# TPS53819A-5v.net
KiCad netlist of a schematic drawn in EAGLE
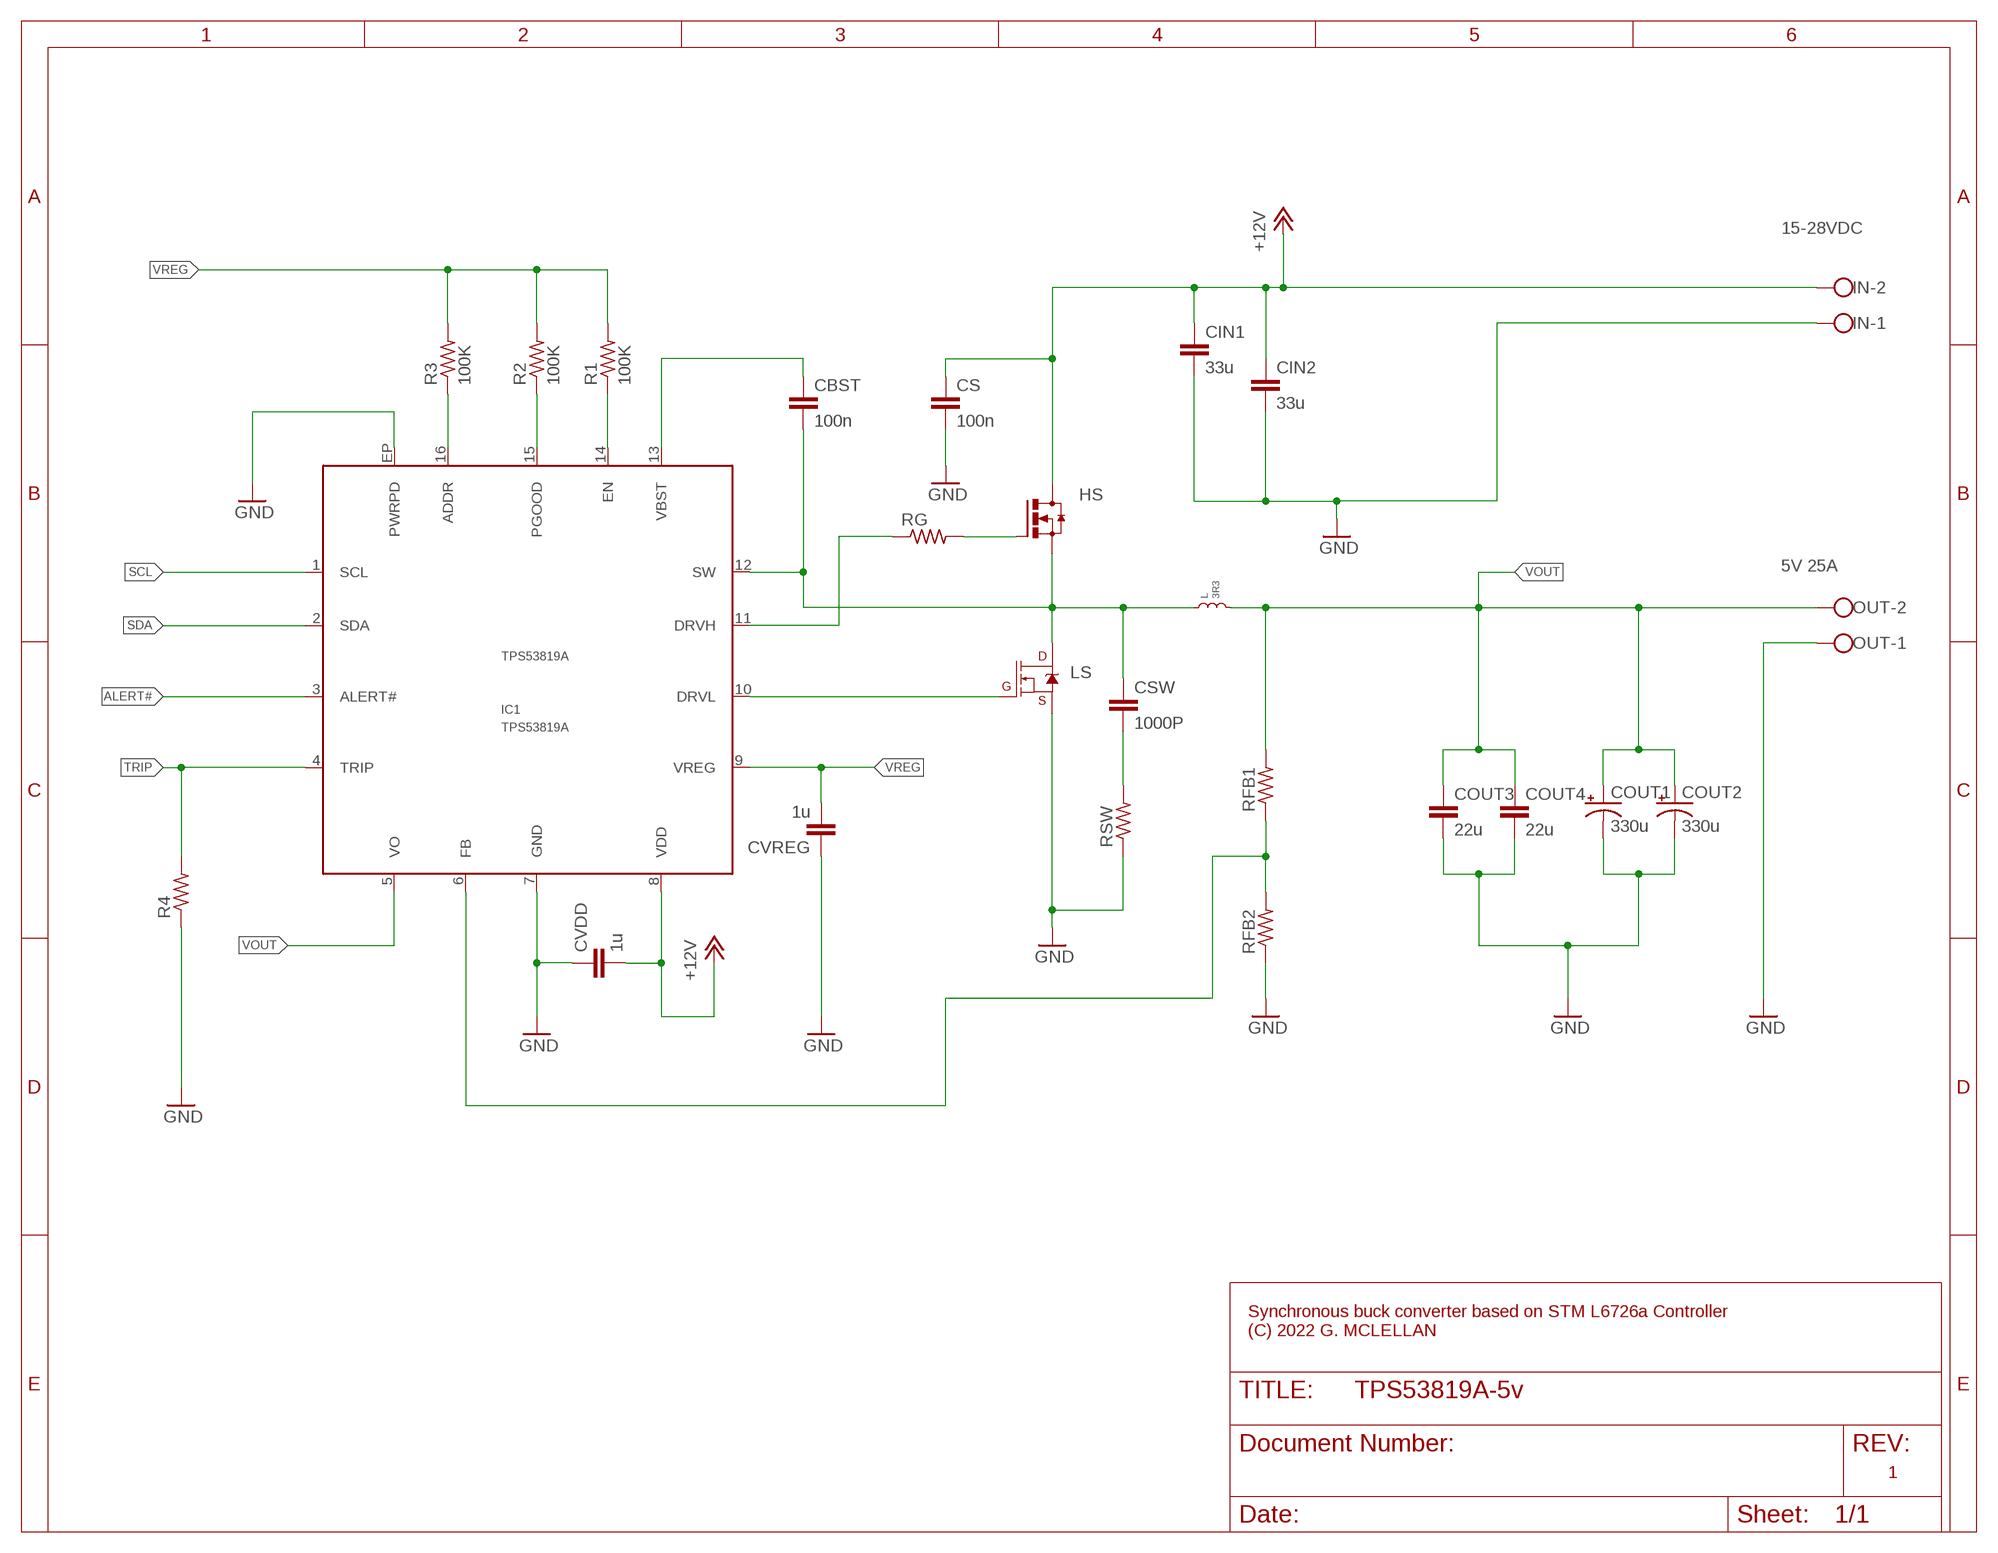
[diagram p0: schematic, sheet 1]

(export (version "E")
  (design (tool "Eeschema 10.0.6"))
  (components
    (comp (ref "CBST")
      (value "100n")
      (footprint "eagle-import:C0603")
      (libsource (lib "eagle-import") (part "C-EUC0603"))
    )
    (comp (ref "CIN1")
      (value "33u")
      (footprint "eagle-import:C2220K")
      (libsource (lib "eagle-import") (part "C-EUC2220K"))
    )
    (comp (ref "CIN2")
      (value "33u")
      (footprint "eagle-import:C2220K")
      (libsource (lib "eagle-import") (part "C-EUC2220K"))
    )
    (comp (ref "COUT1")
      (value "330u")
      (footprint "eagle-import:SANYO-OSCON_SMD_C6")
      (libsource (lib "eagle-import") (part "CPOL-USSANYO_SMD_C6"))
    )
    (comp (ref "COUT2")
      (value "330u")
      (footprint "eagle-import:SANYO-OSCON_SMD_C6")
      (libsource (lib "eagle-import") (part "CPOL-USSANYO_SMD_C6"))
    )
    (comp (ref "COUT3")
      (value "22u")
      (footprint "eagle-import:C1206")
      (libsource (lib "eagle-import") (part "C-EUC1206"))
    )
    (comp (ref "COUT4")
      (value "22u")
      (footprint "eagle-import:C1206")
      (libsource (lib "eagle-import") (part "C-EUC1206"))
    )
    (comp (ref "CS")
      (value "100n")
      (footprint "eagle-import:C0805")
      (libsource (lib "eagle-import") (part "C-EUC0805"))
    )
    (comp (ref "CSW")
      (value "1000P")
      (footprint "eagle-import:C0603")
      (libsource (lib "eagle-import") (part "C-EUC0603"))
    )
    (comp (ref "CVDD")
      (value "1u")
      (footprint "eagle-import:C0805")
      (libsource (lib "eagle-import") (part "C-EUC0805"))
    )
    (comp (ref "CVREG")
      (value "1u")
      (footprint "eagle-import:C0603")
      (libsource (lib "eagle-import") (part "C-EUC0603"))
    )
    (comp (ref "HS")
      (value "N_MOSFET_POWERSO8")
      (footprint "eagle-import:POWERSO8")
      (libsource (lib "eagle-import") (part "N_MOSFET_POWERSO8"))
    )
    (comp (ref "IC1")
      (value "TPS53819A")
      (footprint "eagle-import:QFN-16")
      (libsource (lib "eagle-import") (part "TPS53819A"))
    )
    (comp (ref "IN")
      (value "W237-102")
      (footprint "eagle-import:W237-102")
      (fields (field (name "MPN") "237-102"))
      (libsource (lib "eagle-import") (part "W237-102"))
    )
    (comp (ref "L")
      (value "3R3")
      (footprint "eagle-import:XAL1010")
      (libsource (lib "eagle-import") (part "INDUCTOR.XAL1010"))
    )
    (comp (ref "LS")
      (value "MOSFET-NCH-FDS6630A")
      (footprint "eagle-import:SO08")
      (libsource (lib "eagle-import") (part "MOSFET-NCH-FDS6630A"))
    )
    (comp (ref "OUT")
      (value "W237-102")
      (footprint "eagle-import:W237-102")
      (fields (field (name "MPN") "237-102"))
      (libsource (lib "eagle-import") (part "W237-102"))
    )
    (comp (ref "R1")
      (value "100K")
      (footprint "eagle-import:R0603")
      (libsource (lib "eagle-import") (part "R-US_R0603"))
    )
    (comp (ref "R2")
      (value "100K")
      (footprint "eagle-import:R0603")
      (libsource (lib "eagle-import") (part "R-US_R0603"))
    )
    (comp (ref "R3")
      (value "100K")
      (footprint "eagle-import:R0603")
      (libsource (lib "eagle-import") (part "R-US_R0603"))
    )
    (comp (ref "R4")
      (value "R-US_R0603")
      (footprint "eagle-import:R0603")
      (libsource (lib "eagle-import") (part "R-US_R0603"))
    )
    (comp (ref "RFB1")
      (value "R-US_R0805")
      (footprint "eagle-import:R0805")
      (libsource (lib "eagle-import") (part "R-US_R0805"))
    )
    (comp (ref "RFB2")
      (value "R-US_R0805")
      (footprint "eagle-import:R0805")
      (libsource (lib "eagle-import") (part "R-US_R0805"))
    )
    (comp (ref "RG")
      (value "R-US_R0603")
      (footprint "eagle-import:R0603")
      (libsource (lib "eagle-import") (part "R-US_R0603"))
    )
    (comp (ref "RSW")
      (value "R-US_R0603")
      (footprint "eagle-import:R0603")
      (libsource (lib "eagle-import") (part "R-US_R0603"))
    )
  )
  (nets
    (net (code "1") (name "+12V") (class "Default")
      (node (ref "CIN1") (pin "1") (pinfunction "1_1") (pintype "passive"))
      (node (ref "CIN2") (pin "1") (pinfunction "1_1") (pintype "passive"))
      (node (ref "CS") (pin "1") (pinfunction "1_1") (pintype "passive"))
      (node (ref "CVDD") (pin "2") (pinfunction "2_2") (pintype "passive"))
      (node (ref "HS") (pin "5") (pinfunction "D_5") (pintype "passive"))
      (node (ref "HS") (pin "6") (pinfunction "D_6") (pintype "passive"))
      (node (ref "HS") (pin "7") (pinfunction "D_7") (pintype "passive"))
      (node (ref "HS") (pin "8") (pinfunction "D_8") (pintype "passive"))
      (node (ref "HS") (pin "PAD") (pinfunction "D_PAD") (pintype "passive"))
      (node (ref "IC1") (pin "8") (pinfunction "VDD_8") (pintype "power_in"))
      (node (ref "IN") (pin "2") (pinfunction "KL_2") (pintype "passive"))
    )
    (net (code "2") (name "ALERT#") (class "Default")
      (node (ref "IC1") (pin "3") (pinfunction "ALERT#_3") (pintype "output"))
    )
    (net (code "3") (name "GND") (class "Default")
      (node (ref "CIN1") (pin "2") (pinfunction "2_2") (pintype "passive"))
      (node (ref "CIN2") (pin "2") (pinfunction "2_2") (pintype "passive"))
      (node (ref "COUT1") (pin "-") (pinfunction "-_-") (pintype "passive"))
      (node (ref "COUT2") (pin "-") (pinfunction "-_-") (pintype "passive"))
      (node (ref "COUT3") (pin "2") (pinfunction "2_2") (pintype "passive"))
      (node (ref "COUT4") (pin "2") (pinfunction "2_2") (pintype "passive"))
      (node (ref "CS") (pin "2") (pinfunction "2_2") (pintype "passive"))
      (node (ref "CVDD") (pin "1") (pinfunction "1_1") (pintype "passive"))
      (node (ref "CVREG") (pin "1") (pinfunction "1_1") (pintype "passive"))
      (node (ref "IC1") (pin "7") (pinfunction "GND_7") (pintype "power_in"))
      (node (ref "IC1") (pin "EP") (pinfunction "PWRPD_EP") (pintype "power_in"))
      (node (ref "IN") (pin "1") (pinfunction "KL_1") (pintype "passive"))
      (node (ref "LS") (pin "1") (pinfunction "S_1") (pintype "bidirectional"))
      (node (ref "LS") (pin "2") (pinfunction "S_2") (pintype "bidirectional"))
      (node (ref "LS") (pin "3") (pinfunction "S_3") (pintype "bidirectional"))
      (node (ref "OUT") (pin "1") (pinfunction "KL_1") (pintype "passive"))
      (node (ref "R4") (pin "1") (pinfunction "1_1") (pintype "passive"))
      (node (ref "RFB2") (pin "1") (pinfunction "1_1") (pintype "passive"))
      (node (ref "RSW") (pin "1") (pinfunction "1_1") (pintype "passive"))
    )
    (net (code "4") (name "Net-(CSW-Pad2)") (class "Default")
      (node (ref "CSW") (pin "2") (pinfunction "2_2") (pintype "passive"))
      (node (ref "RSW") (pin "2") (pinfunction "2_2") (pintype "passive"))
    )
    (net (code "5") (name "Net-(HS-G)") (class "Default")
      (node (ref "HS") (pin "4") (pinfunction "G_4") (pintype "passive"))
      (node (ref "RG") (pin "2") (pinfunction "2_2") (pintype "passive"))
    )
    (net (code "6") (name "Net-(IC1-ADDR)") (class "Default")
      (node (ref "IC1") (pin "16") (pinfunction "ADDR_16") (pintype "input"))
      (node (ref "R3") (pin "1") (pinfunction "1_1") (pintype "passive"))
    )
    (net (code "7") (name "Net-(IC1-DRVH)") (class "Default")
      (node (ref "IC1") (pin "11") (pinfunction "DRVH_11") (pintype "output"))
      (node (ref "RG") (pin "1") (pinfunction "1_1") (pintype "passive"))
    )
    (net (code "8") (name "Net-(IC1-DRVL)") (class "Default")
      (node (ref "IC1") (pin "10") (pinfunction "DRVL_10") (pintype "output"))
      (node (ref "LS") (pin "4") (pinfunction "G_4") (pintype "bidirectional"))
    )
    (net (code "9") (name "Net-(IC1-EN)") (class "Default")
      (node (ref "IC1") (pin "14") (pinfunction "EN_14") (pintype "input"))
      (node (ref "R1") (pin "1") (pinfunction "1_1") (pintype "passive"))
    )
    (net (code "10") (name "Net-(IC1-FB)") (class "Default")
      (node (ref "IC1") (pin "6") (pinfunction "FB_6") (pintype "input"))
      (node (ref "RFB1") (pin "1") (pinfunction "1_1") (pintype "passive"))
      (node (ref "RFB2") (pin "2") (pinfunction "2_2") (pintype "passive"))
    )
    (net (code "11") (name "Net-(IC1-PGOOD)") (class "Default")
      (node (ref "IC1") (pin "15") (pinfunction "PGOOD_15") (pintype "output"))
      (node (ref "R2") (pin "1") (pinfunction "1_1") (pintype "passive"))
    )
    (net (code "12") (name "Net-(IC1-SW)") (class "Default")
      (node (ref "CBST") (pin "2") (pinfunction "2_2") (pintype "passive"))
      (node (ref "CSW") (pin "1") (pinfunction "1_1") (pintype "passive"))
      (node (ref "HS") (pin "1") (pinfunction "S_1") (pintype "passive"))
      (node (ref "HS") (pin "2") (pinfunction "S_2") (pintype "passive"))
      (node (ref "HS") (pin "3") (pinfunction "S_3") (pintype "passive"))
      (node (ref "IC1") (pin "12") (pinfunction "SW_12") (pintype "output"))
      (node (ref "L") (pin "P$1") (pinfunction "1_P$1") (pintype "passive"))
      (node (ref "LS") (pin "5") (pinfunction "D_5") (pintype "bidirectional"))
      (node (ref "LS") (pin "6") (pinfunction "D_6") (pintype "bidirectional"))
      (node (ref "LS") (pin "7") (pinfunction "D_7") (pintype "bidirectional"))
      (node (ref "LS") (pin "8") (pinfunction "D_8") (pintype "bidirectional"))
    )
    (net (code "13") (name "Net-(IC1-VBST)") (class "Default")
      (node (ref "CBST") (pin "1") (pinfunction "1_1") (pintype "passive"))
      (node (ref "IC1") (pin "13") (pinfunction "VBST_13") (pintype "power_in"))
    )
    (net (code "14") (name "SCL") (class "Default")
      (node (ref "IC1") (pin "1") (pinfunction "SCL_1") (pintype "bidirectional"))
    )
    (net (code "15") (name "SDA") (class "Default")
      (node (ref "IC1") (pin "2") (pinfunction "SDA_2") (pintype "bidirectional"))
    )
    (net (code "16") (name "TRIP") (class "Default")
      (node (ref "IC1") (pin "4") (pinfunction "TRIP_4") (pintype "output"))
      (node (ref "R4") (pin "2") (pinfunction "2_2") (pintype "passive"))
    )
    (net (code "17") (name "VOUT") (class "Default")
      (node (ref "COUT1") (pin "+") (pinfunction "+_+") (pintype "passive"))
      (node (ref "COUT2") (pin "+") (pinfunction "+_+") (pintype "passive"))
      (node (ref "COUT3") (pin "1") (pinfunction "1_1") (pintype "passive"))
      (node (ref "COUT4") (pin "1") (pinfunction "1_1") (pintype "passive"))
      (node (ref "IC1") (pin "5") (pinfunction "VO_5") (pintype "input"))
      (node (ref "L") (pin "P$2") (pinfunction "2_P$2") (pintype "passive"))
      (node (ref "OUT") (pin "2") (pinfunction "KL_2") (pintype "passive"))
      (node (ref "RFB1") (pin "2") (pinfunction "2_2") (pintype "passive"))
    )
    (net (code "18") (name "VREG") (class "Default")
      (node (ref "CVREG") (pin "2") (pinfunction "2_2") (pintype "passive"))
      (node (ref "IC1") (pin "9") (pinfunction "VREG_9") (pintype "power_in"))
      (node (ref "R1") (pin "2") (pinfunction "2_2") (pintype "passive"))
      (node (ref "R2") (pin "2") (pinfunction "2_2") (pintype "passive"))
      (node (ref "R3") (pin "2") (pinfunction "2_2") (pintype "passive"))
    )
  )
)
